# Device_board_191219.net
KiCad netlist of a schematic drawn in EAGLE
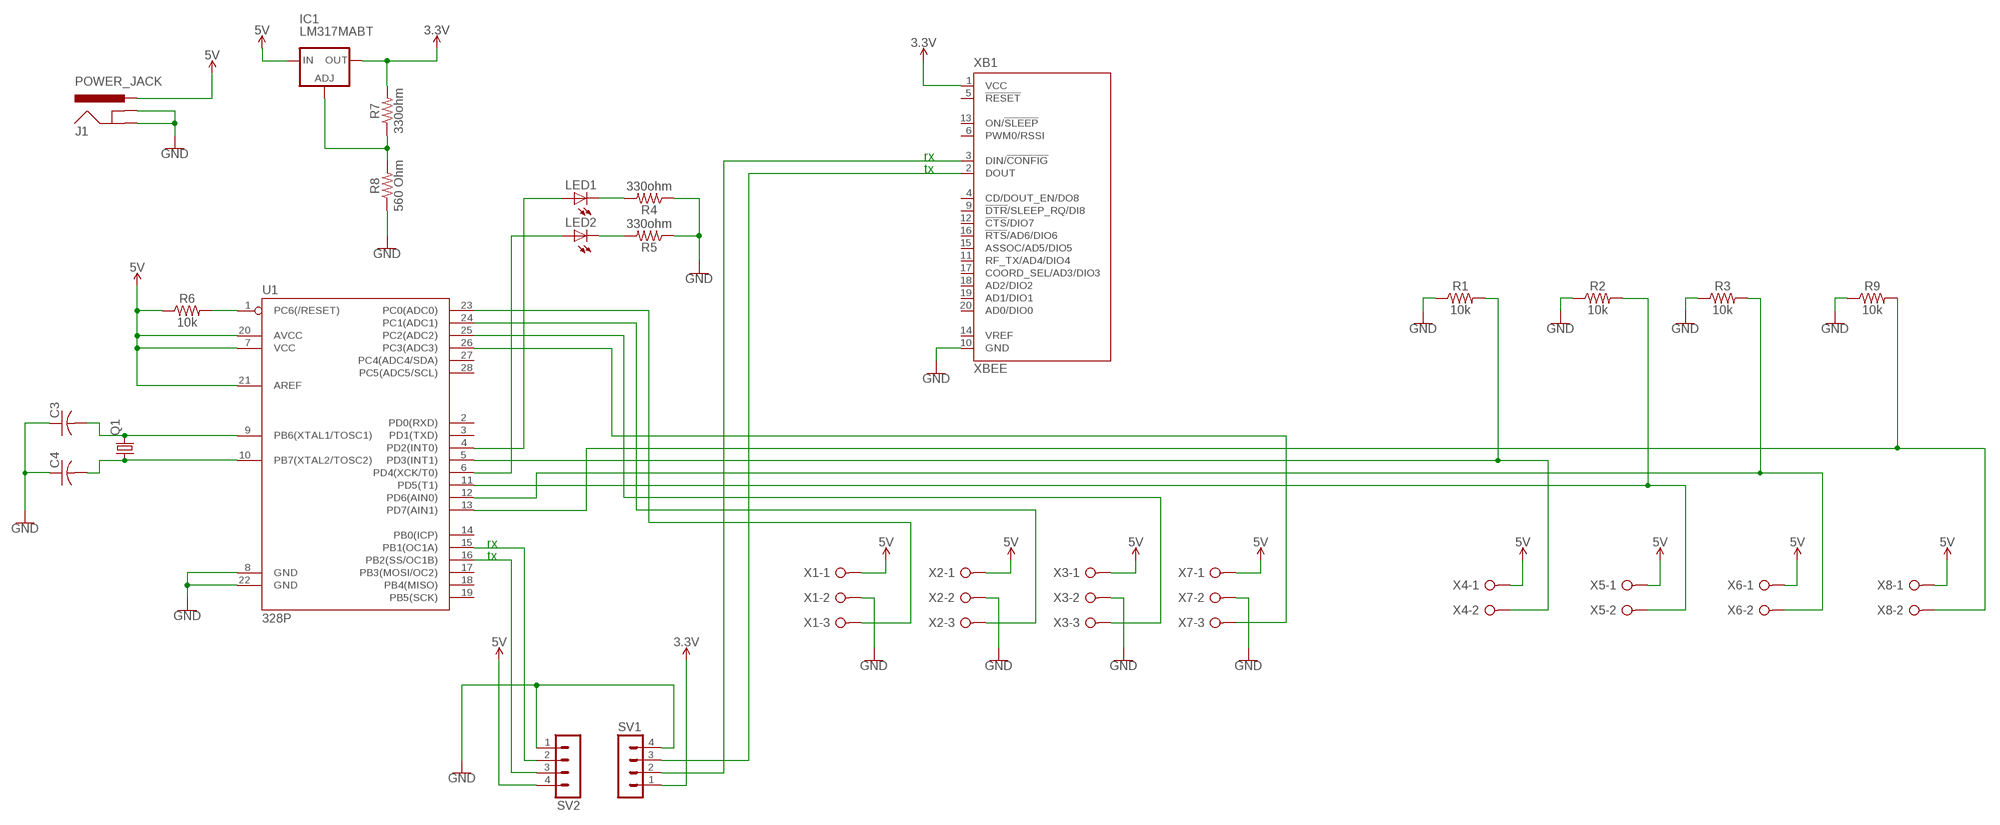
[diagram p0: schematic, sheet 1]

(export (version "E")
  (design (tool "Eeschema 10.0.6"))
  (components
    (comp (ref "C3")
      (value "C-US050-025X075")
      (footprint "eagle-import:C050-025X075")
      (libsource (lib "eagle-import") (part "C-US050-025X075"))
    )
    (comp (ref "C4")
      (value "C-US050-025X075")
      (footprint "eagle-import:C050-025X075")
      (libsource (lib "eagle-import") (part "C-US050-025X075"))
    )
    (comp (ref "IC1")
      (value "LM317MABT")
      (footprint "eagle-import:TO220L1")
      (libsource (lib "eagle-import") (part "LM317?MABT"))
    )
    (comp (ref "J1")
      (value "POWER_JACK")
      (footprint "eagle-import:POWER_JACK_PTH")
      (libsource (lib "eagle-import") (part "POWER_JACK"))
    )
    (comp (ref "LED1")
      (value "LED3MM")
      (footprint "eagle-import:LED3MM")
      (libsource (lib "eagle-import") (part "LED3MM"))
    )
    (comp (ref "LED2")
      (value "LED3MM")
      (footprint "eagle-import:LED3MM")
      (libsource (lib "eagle-import") (part "LED3MM"))
    )
    (comp (ref "Q1")
      (value "CRYSTALHC49S")
      (footprint "eagle-import:HC49_S")
      (libsource (lib "eagle-import") (part "CRYSTALHC49S"))
    )
    (comp (ref "R1")
      (value "10k")
      (footprint "eagle-import:AXIAL-0.3")
      (libsource (lib "eagle-import") (part "10KOHM-HORIZ-1/4W-5%"))
    )
    (comp (ref "R2")
      (value "10k")
      (footprint "eagle-import:AXIAL-0.3")
      (libsource (lib "eagle-import") (part "10KOHM-HORIZ-1/4W-5%"))
    )
    (comp (ref "R3")
      (value "10k")
      (footprint "eagle-import:AXIAL-0.3")
      (libsource (lib "eagle-import") (part "10KOHM-HORIZ-1/4W-5%"))
    )
    (comp (ref "R4")
      (value "330ohm")
      (footprint "eagle-import:AXIAL-0.3")
      (libsource (lib "eagle-import") (part "10KOHM-HORIZ-1/4W-5%"))
    )
    (comp (ref "R5")
      (value "330ohm")
      (footprint "eagle-import:AXIAL-0.3")
      (libsource (lib "eagle-import") (part "10KOHM-HORIZ-1/4W-5%"))
    )
    (comp (ref "R6")
      (value "10k")
      (footprint "eagle-import:AXIAL-0.3")
      (libsource (lib "eagle-import") (part "10KOHM-HORIZ-1/4W-5%"))
    )
    (comp (ref "R7")
      (value "330ohm")
      (footprint "eagle-import:AXIAL-0.3")
      (libsource (lib "eagle-import") (part "10KOHM-HORIZ-1/4W-5%"))
    )
    (comp (ref "R8")
      (value "560 Ohm")
      (footprint "eagle-import:AXIAL-0.3")
      (libsource (lib "eagle-import") (part "10KOHM-HORIZ-1/4W-5%"))
    )
    (comp (ref "R9")
      (value "10k")
      (footprint "eagle-import:AXIAL-0.3")
      (libsource (lib "eagle-import") (part "10KOHM-HORIZ-1/4W-5%"))
    )
    (comp (ref "SV1")
      (value "MA04-1")
      (footprint "eagle-import:MA04-1")
      (libsource (lib "eagle-import") (part "MA04-1"))
    )
    (comp (ref "SV2")
      (value "MA04-1")
      (footprint "eagle-import:MA04-1")
      (libsource (lib "eagle-import") (part "MA04-1"))
    )
    (comp (ref "U1")
      (value "328P")
      (footprint "eagle-import:DIP28")
      (libsource (lib "eagle-import") (part "ATMEGA328P_PDIP"))
    )
    (comp (ref "X1")
      (value "W237-3E")
      (footprint "eagle-import:W237-3E")
      (libsource (lib "eagle-import") (part "W237-3E"))
    )
    (comp (ref "X2")
      (value "W237-3E")
      (footprint "eagle-import:W237-3E")
      (libsource (lib "eagle-import") (part "W237-3E"))
    )
    (comp (ref "X3")
      (value "W237-3E")
      (footprint "eagle-import:W237-3E")
      (libsource (lib "eagle-import") (part "W237-3E"))
    )
    (comp (ref "X4")
      (value "W237-02P")
      (footprint "eagle-import:W237-132")
      (libsource (lib "eagle-import") (part "W237-02P"))
    )
    (comp (ref "X5")
      (value "W237-02P")
      (footprint "eagle-import:W237-132")
      (libsource (lib "eagle-import") (part "W237-02P"))
    )
    (comp (ref "X6")
      (value "W237-02P")
      (footprint "eagle-import:W237-132")
      (libsource (lib "eagle-import") (part "W237-02P"))
    )
    (comp (ref "X7")
      (value "W237-3E")
      (footprint "eagle-import:W237-3E")
      (libsource (lib "eagle-import") (part "W237-3E"))
    )
    (comp (ref "X8")
      (value "W237-02P")
      (footprint "eagle-import:W237-132")
      (libsource (lib "eagle-import") (part "W237-02P"))
    )
    (comp (ref "XB1")
      (value "XBEE")
      (footprint "eagle-import:XBEE")
      (fields (field (name "MPN") "XBP24-Z7UIT-004"))
      (libsource (lib "eagle-import") (part "XBEE"))
    )
  )
  (nets
    (net (code "1") (name "3.3V") (class "Default")
      (node (ref "IC1") (pin "2") (pinfunction "OUT_2") (pintype "passive"))
      (node (ref "R7") (pin "P$2") (pinfunction "2_P$2") (pintype "passive"))
      (node (ref "SV1") (pin "1") (pinfunction "1_1") (pintype "passive"))
      (node (ref "XB1") (pin "1") (pinfunction "VCC_1") (pintype "power_in"))
    )
    (net (code "2") (name "5V") (class "Default")
      (node (ref "IC1") (pin "3") (pinfunction "IN_3") (pintype "input"))
      (node (ref "J1") (pin "PWR") (pinfunction "PWR_PWR") (pintype "bidirectional"))
      (node (ref "R6") (pin "P$1") (pinfunction "1_P$1") (pintype "passive"))
      (node (ref "SV2") (pin "4") (pinfunction "4_4") (pintype "passive"))
      (node (ref "U1") (pin "20") (pinfunction "AVCC_20") (pintype "bidirectional"))
      (node (ref "U1") (pin "21") (pinfunction "AREF_21") (pintype "bidirectional"))
      (node (ref "U1") (pin "7") (pinfunction "VCC_7") (pintype "bidirectional"))
      (node (ref "X1") (pin "1") (pinfunction "KL_1") (pintype "passive"))
      (node (ref "X2") (pin "1") (pinfunction "KL_1") (pintype "passive"))
      (node (ref "X3") (pin "1") (pinfunction "KL_1") (pintype "passive"))
      (node (ref "X4") (pin "1") (pinfunction "KL_1") (pintype "passive"))
      (node (ref "X5") (pin "1") (pinfunction "KL_1") (pintype "passive"))
      (node (ref "X6") (pin "1") (pinfunction "KL_1") (pintype "passive"))
      (node (ref "X7") (pin "1") (pinfunction "KL_1") (pintype "passive"))
      (node (ref "X8") (pin "1") (pinfunction "KL_1") (pintype "passive"))
    )
    (net (code "3") (name "GND") (class "Default")
      (node (ref "C3") (pin "1") (pinfunction "1_1") (pintype "passive"))
      (node (ref "C4") (pin "1") (pinfunction "1_1") (pintype "passive"))
      (node (ref "J1") (pin "GND") (pinfunction "GND_GND") (pintype "bidirectional"))
      (node (ref "J1") (pin "GNDBREAK") (pinfunction "GNDBREAK_GNDBREAK") (pintype "bidirectional"))
      (node (ref "R1") (pin "P$1") (pinfunction "1_P$1") (pintype "passive"))
      (node (ref "R2") (pin "P$1") (pinfunction "1_P$1") (pintype "passive"))
      (node (ref "R3") (pin "P$1") (pinfunction "1_P$1") (pintype "passive"))
      (node (ref "R4") (pin "P$1") (pinfunction "1_P$1") (pintype "passive"))
      (node (ref "R5") (pin "P$1") (pinfunction "1_P$1") (pintype "passive"))
      (node (ref "R8") (pin "P$1") (pinfunction "1_P$1") (pintype "passive"))
      (node (ref "R9") (pin "P$1") (pinfunction "1_P$1") (pintype "passive"))
      (node (ref "SV1") (pin "4") (pinfunction "4_4") (pintype "passive"))
      (node (ref "SV2") (pin "1") (pinfunction "1_1") (pintype "passive"))
      (node (ref "U1") (pin "22") (pinfunction "GND_22") (pintype "bidirectional"))
      (node (ref "U1") (pin "8") (pinfunction "GND_8") (pintype "bidirectional"))
      (node (ref "X1") (pin "2") (pinfunction "KL_2") (pintype "passive"))
      (node (ref "X2") (pin "2") (pinfunction "KL_2") (pintype "passive"))
      (node (ref "X3") (pin "2") (pinfunction "KL_2") (pintype "passive"))
      (node (ref "X7") (pin "2") (pinfunction "KL_2") (pintype "passive"))
      (node (ref "XB1") (pin "10") (pinfunction "GND_10") (pintype "power_in"))
    )
    (net (code "4") (name "Net-(IC1-ADJ)") (class "Default")
      (node (ref "IC1") (pin "1") (pinfunction "ADJ_1") (pintype "input"))
      (node (ref "R7") (pin "P$1") (pinfunction "1_P$1") (pintype "passive"))
      (node (ref "R8") (pin "P$2") (pinfunction "2_P$2") (pintype "passive"))
    )
    (net (code "5") (name "Net-(LED1-C)") (class "Default")
      (node (ref "LED1") (pin "K") (pinfunction "C_K") (pintype "passive"))
      (node (ref "R4") (pin "P$2") (pinfunction "2_P$2") (pintype "passive"))
    )
    (net (code "6") (name "Net-(LED2-C)") (class "Default")
      (node (ref "LED2") (pin "K") (pinfunction "C_K") (pintype "passive"))
      (node (ref "R5") (pin "P$2") (pinfunction "2_P$2") (pintype "passive"))
    )
    (net (code "7") (name "Net-(R1-2)") (class "Default")
      (node (ref "R1") (pin "P$2") (pinfunction "2_P$2") (pintype "passive"))
      (node (ref "U1") (pin "5") (pinfunction "PD3(INT1)_5") (pintype "bidirectional"))
      (node (ref "X4") (pin "2") (pinfunction "KL_2") (pintype "passive"))
    )
    (net (code "8") (name "Net-(R2-2)") (class "Default")
      (node (ref "R2") (pin "P$2") (pinfunction "2_P$2") (pintype "passive"))
      (node (ref "U1") (pin "11") (pinfunction "PD5(T1)_11") (pintype "bidirectional"))
      (node (ref "X5") (pin "2") (pinfunction "KL_2") (pintype "passive"))
    )
    (net (code "9") (name "Net-(R3-2)") (class "Default")
      (node (ref "R3") (pin "P$2") (pinfunction "2_P$2") (pintype "passive"))
      (node (ref "U1") (pin "12") (pinfunction "PD6(AIN0)_12") (pintype "bidirectional"))
      (node (ref "X6") (pin "2") (pinfunction "KL_2") (pintype "passive"))
    )
    (net (code "10") (name "Net-(R6-2)") (class "Default")
      (node (ref "R6") (pin "P$2") (pinfunction "2_P$2") (pintype "passive"))
      (node (ref "U1") (pin "1") (pinfunction "PC6(/RESET)_1") (pintype "bidirectional"))
    )
    (net (code "11") (name "Net-(R9-2)") (class "Default")
      (node (ref "R9") (pin "P$2") (pinfunction "2_P$2") (pintype "passive"))
      (node (ref "U1") (pin "13") (pinfunction "PD7(AIN1)_13") (pintype "bidirectional"))
      (node (ref "X8") (pin "2") (pinfunction "KL_2") (pintype "passive"))
    )
    (net (code "12") (name "Net-(U1-PB1(OC1A))") (class "Default")
      (node (ref "SV2") (pin "2") (pinfunction "2_2") (pintype "passive"))
      (node (ref "U1") (pin "15") (pinfunction "PB1(OC1A)_15") (pintype "bidirectional"))
    )
    (net (code "13") (name "Net-(U1-PB2(SS{slash}OC1B))") (class "Default")
      (node (ref "SV2") (pin "3") (pinfunction "3_3") (pintype "passive"))
      (node (ref "U1") (pin "16") (pinfunction "PB2(SS/OC1B)_16") (pintype "bidirectional"))
    )
    (net (code "14") (name "Net-(U1-PB6(XTAL1{slash}TOSC1))") (class "Default")
      (node (ref "C3") (pin "2") (pinfunction "2_2") (pintype "passive"))
      (node (ref "Q1") (pin "2") (pinfunction "2_2") (pintype "passive"))
      (node (ref "U1") (pin "9") (pinfunction "PB6(XTAL1/TOSC1)_9") (pintype "bidirectional"))
    )
    (net (code "15") (name "Net-(U1-PB7(XTAL2{slash}TOSC2))") (class "Default")
      (node (ref "C4") (pin "2") (pinfunction "2_2") (pintype "passive"))
      (node (ref "Q1") (pin "1") (pinfunction "1_1") (pintype "passive"))
      (node (ref "U1") (pin "10") (pinfunction "PB7(XTAL2/TOSC2)_10") (pintype "bidirectional"))
    )
    (net (code "16") (name "Net-(U1-PC0(ADC0))") (class "Default")
      (node (ref "U1") (pin "23") (pinfunction "PC0(ADC0)_23") (pintype "bidirectional"))
      (node (ref "X1") (pin "3") (pinfunction "KL_3") (pintype "passive"))
    )
    (net (code "17") (name "Net-(U1-PC1(ADC1))") (class "Default")
      (node (ref "U1") (pin "24") (pinfunction "PC1(ADC1)_24") (pintype "bidirectional"))
      (node (ref "X2") (pin "3") (pinfunction "KL_3") (pintype "passive"))
    )
    (net (code "18") (name "Net-(U1-PC2(ADC2))") (class "Default")
      (node (ref "U1") (pin "25") (pinfunction "PC2(ADC2)_25") (pintype "bidirectional"))
      (node (ref "X3") (pin "3") (pinfunction "KL_3") (pintype "passive"))
    )
    (net (code "19") (name "Net-(U1-PC3(ADC3))") (class "Default")
      (node (ref "U1") (pin "26") (pinfunction "PC3(ADC3)_26") (pintype "bidirectional"))
      (node (ref "X7") (pin "3") (pinfunction "KL_3") (pintype "passive"))
    )
    (net (code "20") (name "Net-(U1-PD2(INT0))") (class "Default")
      (node (ref "LED1") (pin "A") (pinfunction "A_A") (pintype "passive"))
      (node (ref "U1") (pin "4") (pinfunction "PD2(INT0)_4") (pintype "bidirectional"))
    )
    (net (code "21") (name "Net-(U1-PD4(XCK{slash}T0))") (class "Default")
      (node (ref "LED2") (pin "A") (pinfunction "A_A") (pintype "passive"))
      (node (ref "U1") (pin "6") (pinfunction "PD4(XCK/T0)_6") (pintype "bidirectional"))
    )
    (net (code "22") (name "Net-(XB1-DIN{slash}~{CONFIG})") (class "Default")
      (node (ref "SV1") (pin "2") (pinfunction "2_2") (pintype "passive"))
      (node (ref "XB1") (pin "3") (pinfunction "DIN/~{CONFIG}_3") (pintype "input"))
    )
    (net (code "23") (name "Net-(XB1-DOUT)") (class "Default")
      (node (ref "SV1") (pin "3") (pinfunction "3_3") (pintype "passive"))
      (node (ref "XB1") (pin "2") (pinfunction "DOUT_2") (pintype "output"))
    )
    (net (code "24") (name "unconnected-(U1-PB0(ICP)-Pad14)") (class "Default")
      (node (ref "U1") (pin "14") (pinfunction "PB0(ICP)_14") (pintype "bidirectional"))
    )
    (net (code "25") (name "unconnected-(U1-PB3(MOSI{slash}OC2)-Pad17)") (class "Default")
      (node (ref "U1") (pin "17") (pinfunction "PB3(MOSI/OC2)_17") (pintype "bidirectional"))
    )
    (net (code "26") (name "unconnected-(U1-PB4(MISO)-Pad18)") (class "Default")
      (node (ref "U1") (pin "18") (pinfunction "PB4(MISO)_18") (pintype "bidirectional"))
    )
    (net (code "27") (name "unconnected-(U1-PB5(SCK)-Pad19)") (class "Default")
      (node (ref "U1") (pin "19") (pinfunction "PB5(SCK)_19") (pintype "bidirectional"))
    )
    (net (code "28") (name "unconnected-(U1-PC4(ADC4{slash}SDA)-Pad27)") (class "Default")
      (node (ref "U1") (pin "27") (pinfunction "PC4(ADC4/SDA)_27") (pintype "bidirectional"))
    )
    (net (code "29") (name "unconnected-(U1-PC5(ADC5{slash}SCL)-Pad28)") (class "Default")
      (node (ref "U1") (pin "28") (pinfunction "PC5(ADC5/SCL)_28") (pintype "bidirectional"))
    )
    (net (code "30") (name "unconnected-(U1-PD0(RXD)-Pad2)") (class "Default")
      (node (ref "U1") (pin "2") (pinfunction "PD0(RXD)_2") (pintype "bidirectional"))
    )
    (net (code "31") (name "unconnected-(U1-PD1(TXD)-Pad3)") (class "Default")
      (node (ref "U1") (pin "3") (pinfunction "PD1(TXD)_3") (pintype "bidirectional"))
    )
    (net (code "32") (name "unconnected-(XB1-AD0{slash}DIO0-Pad20)") (class "Default")
      (node (ref "XB1") (pin "20") (pinfunction "AD0/DIO0_20") (pintype "bidirectional"))
    )
    (net (code "33") (name "unconnected-(XB1-AD1{slash}DIO1-Pad19)") (class "Default")
      (node (ref "XB1") (pin "19") (pinfunction "AD1/DIO1_19") (pintype "bidirectional"))
    )
    (net (code "34") (name "unconnected-(XB1-AD2{slash}DIO2-Pad18)") (class "Default")
      (node (ref "XB1") (pin "18") (pinfunction "AD2/DIO2_18") (pintype "bidirectional"))
    )
    (net (code "35") (name "unconnected-(XB1-ASSOC{slash}AD5{slash}DIO5-Pad15)") (class "Default")
      (node (ref "XB1") (pin "15") (pinfunction "ASSOC/AD5/DIO5_15") (pintype "bidirectional"))
    )
    (net (code "36") (name "unconnected-(XB1-CD{slash}DOUT_EN{slash}DO8-Pad4)") (class "Default")
      (node (ref "XB1") (pin "4") (pinfunction "CD/DOUT_EN/DO8_4") (pintype "output"))
    )
    (net (code "37") (name "unconnected-(XB1-COORD_SEL{slash}AD3{slash}DIO3-Pad17)") (class "Default")
      (node (ref "XB1") (pin "17") (pinfunction "COORD_SEL/AD3/DIO3_17") (pintype "bidirectional"))
    )
    (net (code "38") (name "unconnected-(XB1-ON{slash}~{SLEEP}-Pad13)") (class "Default")
      (node (ref "XB1") (pin "13") (pinfunction "ON/~{SLEEP}_13") (pintype "output"))
    )
    (net (code "39") (name "unconnected-(XB1-PWM0{slash}RSSI-Pad6)") (class "Default")
      (node (ref "XB1") (pin "6") (pinfunction "PWM0/RSSI_6") (pintype "output"))
    )
    (net (code "40") (name "unconnected-(XB1-RF_TX{slash}AD4{slash}DIO4-Pad11)") (class "Default")
      (node (ref "XB1") (pin "11") (pinfunction "RF_TX/AD4/DIO4_11") (pintype "bidirectional"))
    )
    (net (code "41") (name "unconnected-(XB1-VREF-Pad14)") (class "Default")
      (node (ref "XB1") (pin "14") (pinfunction "VREF_14") (pintype "input"))
    )
    (net (code "42") (name "unconnected-(XB1-~{CTS}{slash}DIO7-Pad12)") (class "Default")
      (node (ref "XB1") (pin "12") (pinfunction "~{CTS}/DIO7_12") (pintype "bidirectional"))
    )
    (net (code "43") (name "unconnected-(XB1-~{DTR}{slash}SLEEP_RQ{slash}DI8-Pad9)") (class "Default")
      (node (ref "XB1") (pin "9") (pinfunction "~{DTR}/SLEEP_RQ/DI8_9") (pintype "bidirectional"))
    )
    (net (code "44") (name "unconnected-(XB1-~{RESET}-Pad5)") (class "Default")
      (node (ref "XB1") (pin "5") (pinfunction "~{RESET}_5") (pintype "input"))
    )
    (net (code "45") (name "unconnected-(XB1-~{RTS}{slash}AD6{slash}DIO6-Pad16)") (class "Default")
      (node (ref "XB1") (pin "16") (pinfunction "~{RTS}/AD6/DIO6_16") (pintype "bidirectional"))
    )
  )
)
